# nixie.net
KiCad netlist of a schematic drawn in EAGLE
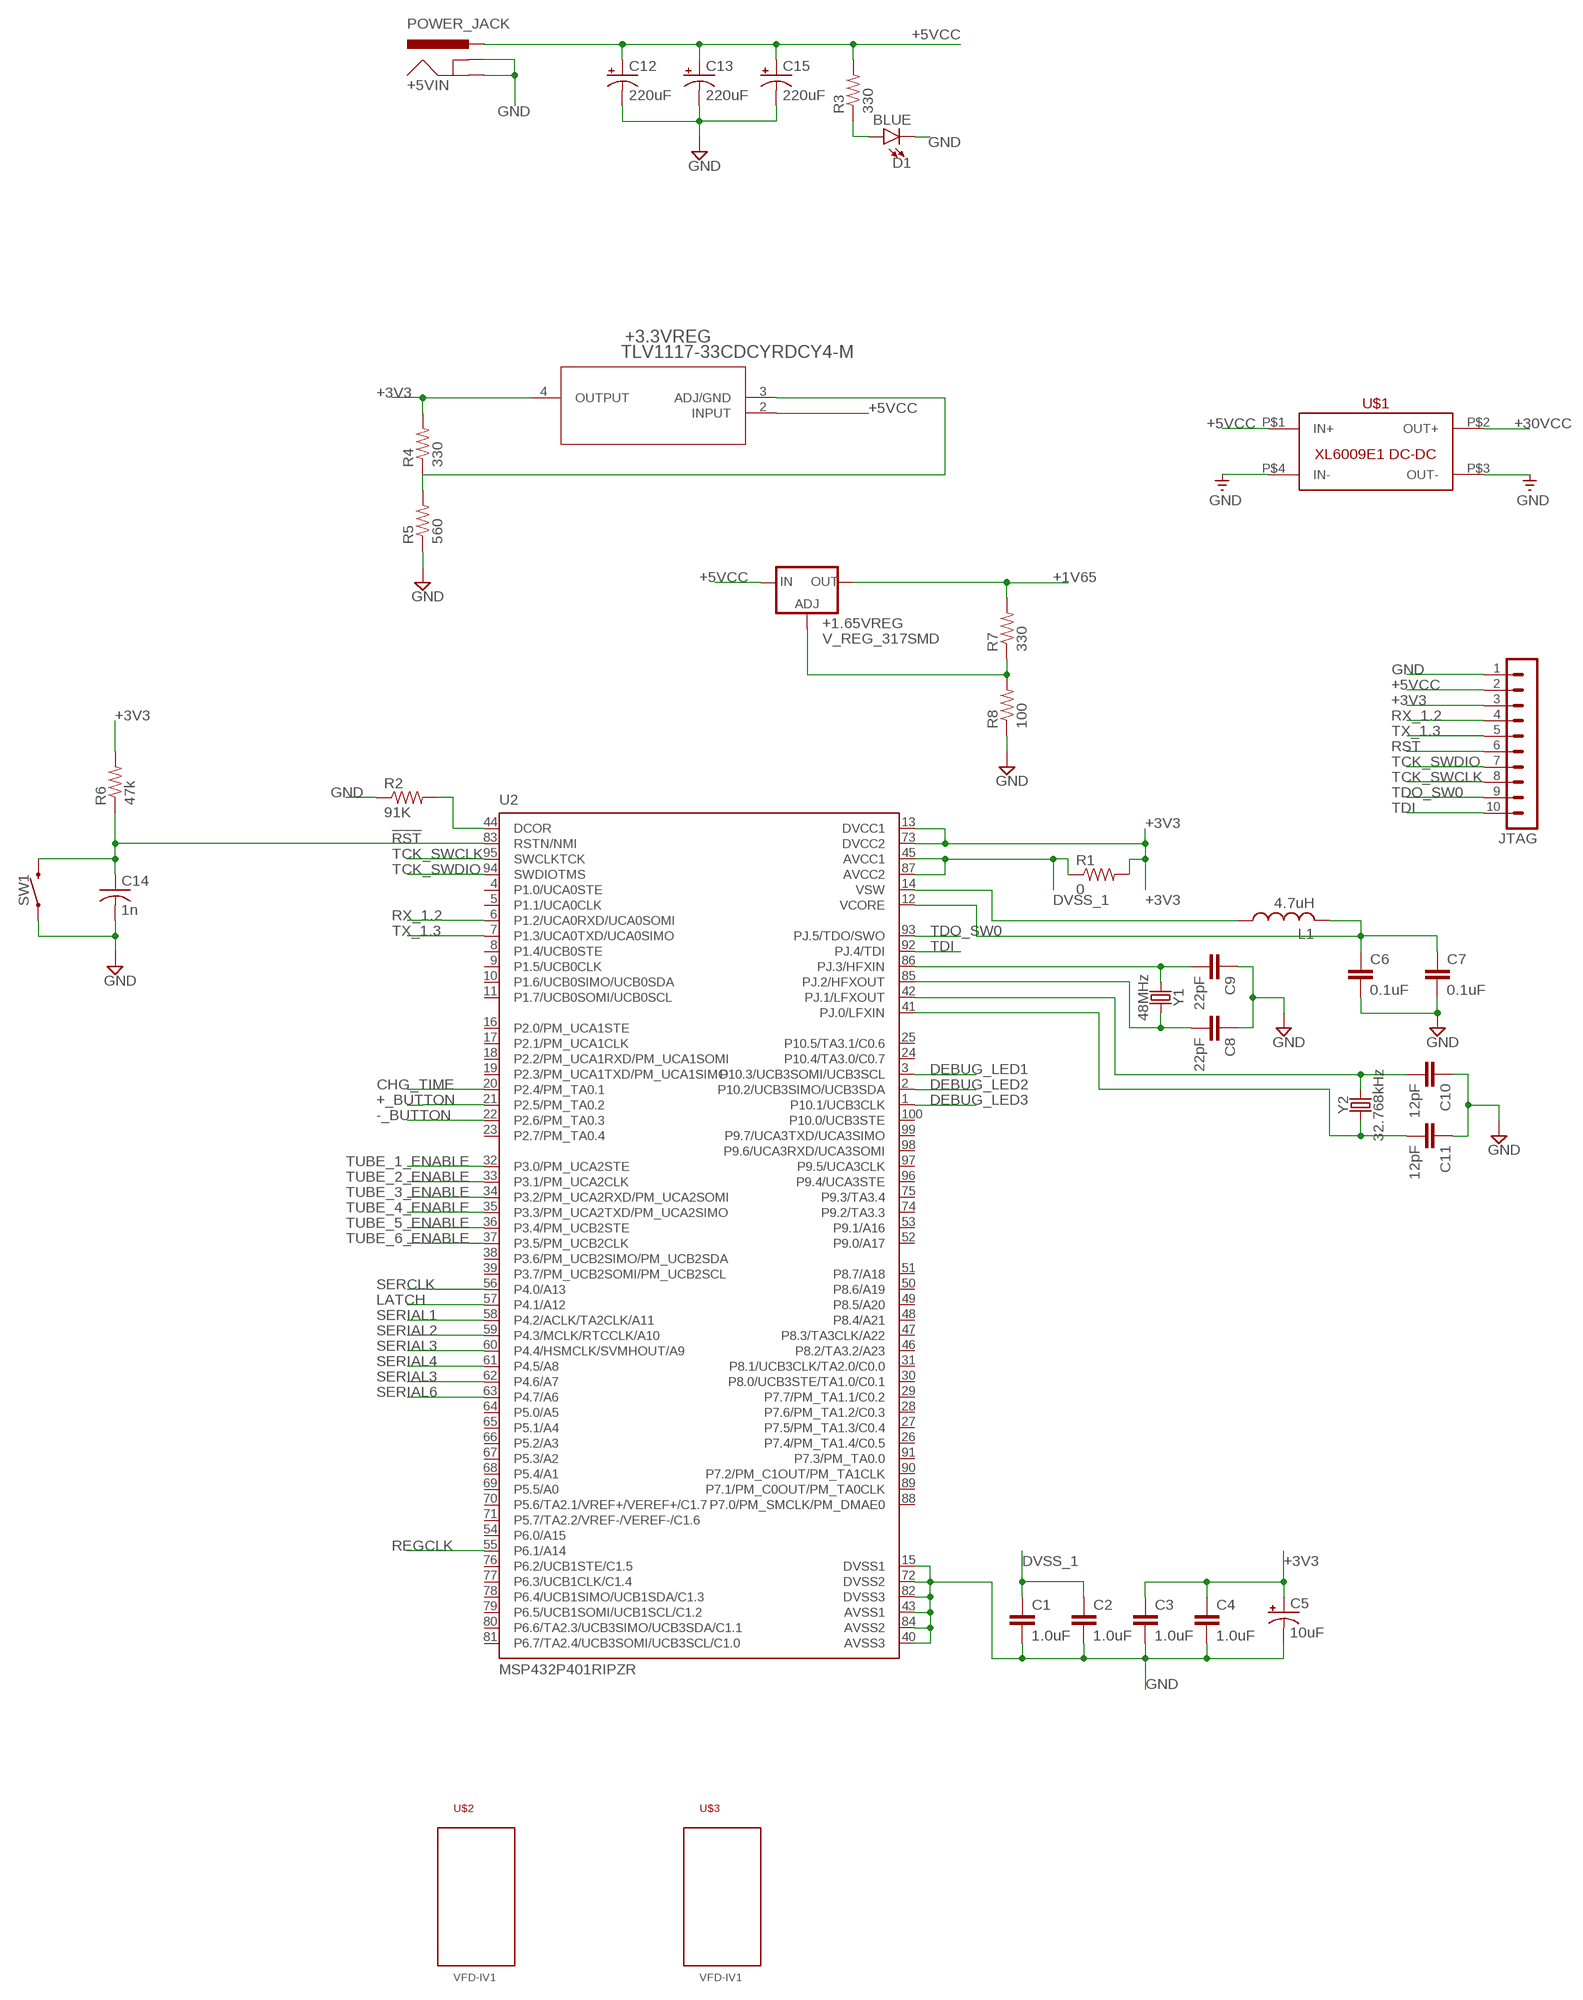
[diagram p0: schematic, sheet 1, part 1 of 2]
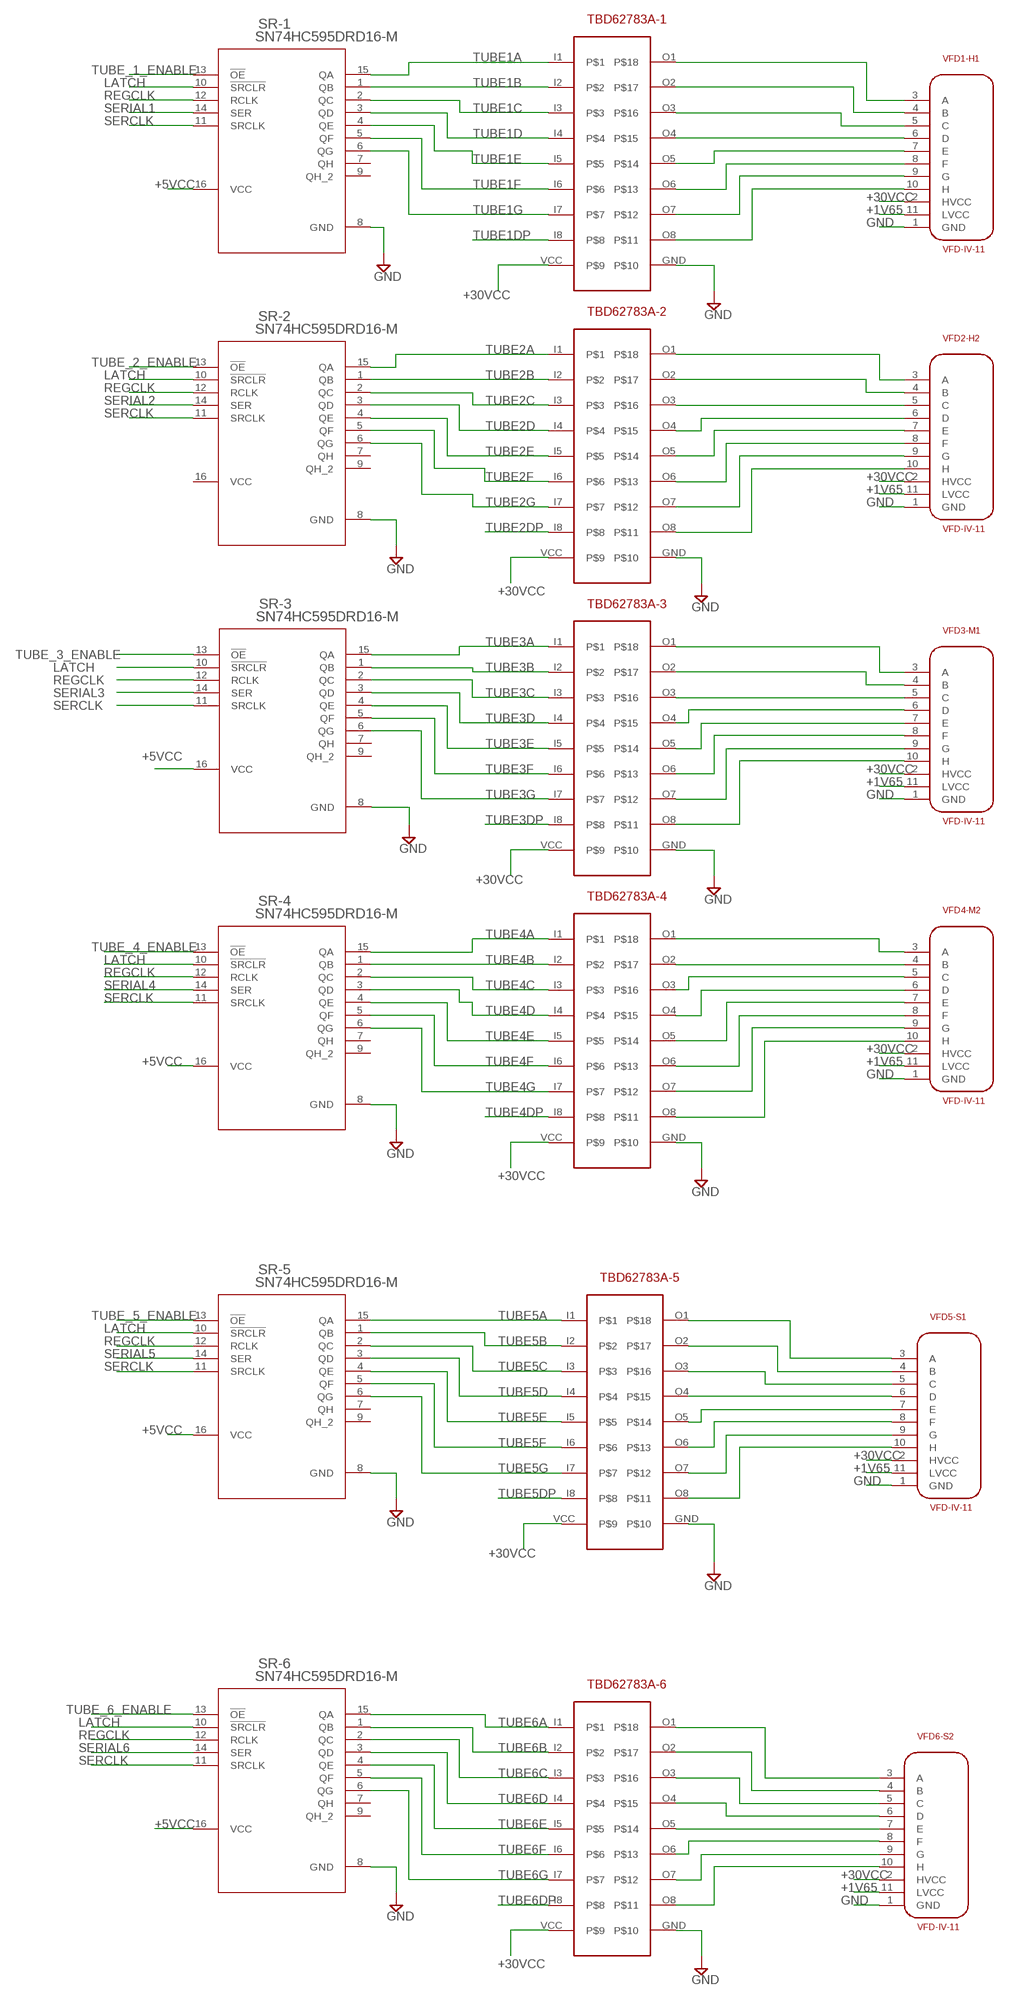
[diagram p1: schematic, sheet 1, part 2 of 2]

(export (version "E")
  (design (tool "Eeschema 10.0.6"))
  (components
    (comp (ref "+1.65VREG")
      (value "V_REG_317SMD")
      (footprint "eagle-import:SOT223")
      (libsource (lib "eagle-import") (part "V_REG_317SMD"))
    )
    (comp (ref "+3.3VREG")
      (value "TLV1117-33CDCYRDCY4-M")
      (footprint "eagle-import:DCY4-M")
      (fields (field (name "MANUFACTURER_PART_NUMBER") "TLV111733CDCYR"))
      (libsource (lib "eagle-import") (part "TLV1117-33CDCYRDCY4-M"))
    )
    (comp (ref "+5VIN")
      (value "POWER_JACK")
      (footprint "eagle-import:POWER_JACK_PTH")
      (libsource (lib "eagle-import") (part "POWER_JACK"))
    )
    (comp (ref "C1")
      (value "1.0uF")
      (footprint "eagle-import:0805")
      (libsource (lib "eagle-import") (part "1.0UF-0805-25V-(+80/-20%)"))
    )
    (comp (ref "C2")
      (value "1.0uF")
      (footprint "eagle-import:0805")
      (libsource (lib "eagle-import") (part "1.0UF-0805-25V-(+80/-20%)"))
    )
    (comp (ref "C3")
      (value "1.0uF")
      (footprint "eagle-import:0805")
      (libsource (lib "eagle-import") (part "1.0UF-0805-25V-(+80/-20%)"))
    )
    (comp (ref "C4")
      (value "1.0uF")
      (footprint "eagle-import:0805")
      (libsource (lib "eagle-import") (part "1.0UF-0805-25V-(+80/-20%)"))
    )
    (comp (ref "C5")
      (value "10uF")
      (footprint "eagle-import:EIA3216")
      (libsource (lib "eagle-import") (part "10UF-POLAR-EIA3216-16V-10%(TANT)"))
    )
    (comp (ref "C6")
      (value "0.1uF")
      (footprint "eagle-import:0603")
      (libsource (lib "eagle-import") (part "0.1UF-0603-25V-(+80/-20%)"))
    )
    (comp (ref "C7")
      (value "0.1uF")
      (footprint "eagle-import:0603")
      (libsource (lib "eagle-import") (part "0.1UF-0603-25V-(+80/-20%)"))
    )
    (comp (ref "C8")
      (value "22pF")
      (footprint "eagle-import:0603")
      (libsource (lib "eagle-import") (part "22PF-0603-50V-5%"))
    )
    (comp (ref "C9")
      (value "22pF")
      (footprint "eagle-import:0603")
      (libsource (lib "eagle-import") (part "22PF-0603-50V-5%"))
    )
    (comp (ref "C10")
      (value "12pF")
      (footprint "eagle-import:0603")
      (libsource (lib "eagle-import") (part "12PF-0603-50V-5%"))
    )
    (comp (ref "C11")
      (value "12pF")
      (footprint "eagle-import:0603")
      (libsource (lib "eagle-import") (part "12PF-0603-50V-5%"))
    )
    (comp (ref "C12")
      (value "220uF")
      (footprint "eagle-import:E2-5")
      (libsource (lib "eagle-import") (part "CPOL-USE2-5"))
    )
    (comp (ref "C13")
      (value "220uF")
      (footprint "eagle-import:E2-5")
      (libsource (lib "eagle-import") (part "CPOL-USE2-5"))
    )
    (comp (ref "C14")
      (value "1n")
      (footprint "eagle-import:C0805K")
      (libsource (lib "eagle-import") (part "C-USC0805K"))
    )
    (comp (ref "C15")
      (value "220uF")
      (footprint "eagle-import:E2-5")
      (libsource (lib "eagle-import") (part "CPOL-USE2-5"))
    )
    (comp (ref "D1")
      (value "BLUE")
      (footprint "eagle-import:LED-1206")
      (libsource (lib "eagle-import") (part "LED-BLUE1206"))
    )
    (comp (ref "JTAG")
      (value "MA10-1")
      (footprint "eagle-import:MA10-1")
      (libsource (lib "eagle-import") (part "MA10-1"))
    )
    (comp (ref "L1")
      (value "4.7uH")
      (footprint "eagle-import:L0603")
      (libsource (lib "eagle-import") (part "L-USL0603"))
    )
    (comp (ref "R1")
      (value "0")
      (footprint "eagle-import:MINI_MELF-0204W")
      (libsource (lib "eagle-import") (part "R-US_MELF0204W"))
    )
    (comp (ref "R2")
      (value "91K")
      (footprint "eagle-import:MINI_MELF-0204W")
      (libsource (lib "eagle-import") (part "R-US_MELF0204W"))
    )
    (comp (ref "R3")
      (value "330")
      (footprint "eagle-import:MINI_MELF-0204W")
      (libsource (lib "eagle-import") (part "R-US_MELF0204W"))
    )
    (comp (ref "R4")
      (value "330")
      (footprint "eagle-import:MINI_MELF-0204W")
      (libsource (lib "eagle-import") (part "R-US_MELF0204W"))
    )
    (comp (ref "R5")
      (value "560")
      (footprint "eagle-import:MINI_MELF-0204W")
      (libsource (lib "eagle-import") (part "R-US_MELF0204W"))
    )
    (comp (ref "R6")
      (value "47k")
      (footprint "eagle-import:MINI_MELF-0204W")
      (libsource (lib "eagle-import") (part "R-US_MELF0204W"))
    )
    (comp (ref "R7")
      (value "330")
      (footprint "eagle-import:MINI_MELF-0204W")
      (libsource (lib "eagle-import") (part "R-US_MELF0204W"))
    )
    (comp (ref "R8")
      (value "100")
      (footprint "eagle-import:MINI_MELF-0204W")
      (libsource (lib "eagle-import") (part "R-US_MELF0204W"))
    )
    (comp (ref "SR-1")
      (value "SN74HC595DRD16-M")
      (footprint "eagle-import:D16-M")
      (fields (field (name "MANUFACTURER_PART_NUMBER") "SN74HC595DR"))
      (libsource (lib "eagle-import") (part "SN74HC595DRD16-M"))
    )
    (comp (ref "SR-2")
      (value "SN74HC595DRD16-M")
      (footprint "eagle-import:D16-M")
      (fields (field (name "MANUFACTURER_PART_NUMBER") "SN74HC595DR"))
      (libsource (lib "eagle-import") (part "SN74HC595DRD16-M"))
    )
    (comp (ref "SR-3")
      (value "SN74HC595DRD16-M")
      (footprint "eagle-import:D16-M")
      (fields (field (name "MANUFACTURER_PART_NUMBER") "SN74HC595DR"))
      (libsource (lib "eagle-import") (part "SN74HC595DRD16-M"))
    )
    (comp (ref "SR-4")
      (value "SN74HC595DRD16-M")
      (footprint "eagle-import:D16-M")
      (fields (field (name "MANUFACTURER_PART_NUMBER") "SN74HC595DR"))
      (libsource (lib "eagle-import") (part "SN74HC595DRD16-M"))
    )
    (comp (ref "SR-5")
      (value "SN74HC595DRD16-M")
      (footprint "eagle-import:D16-M")
      (fields (field (name "MANUFACTURER_PART_NUMBER") "SN74HC595DR"))
      (libsource (lib "eagle-import") (part "SN74HC595DRD16-M"))
    )
    (comp (ref "SR-6")
      (value "SN74HC595DRD16-M")
      (footprint "eagle-import:D16-M")
      (fields (field (name "MANUFACTURER_PART_NUMBER") "SN74HC595DR"))
      (libsource (lib "eagle-import") (part "SN74HC595DRD16-M"))
    )
    (comp (ref "SW1")
      (value "MOMENTARY-SWITCH-SPST-SMD-6.2MM-TALL")
      (footprint "eagle-import:TACTILE_SWITCH_SMD_6.2MM_TALL")
      (libsource (lib "eagle-import") (part "MOMENTARY-SWITCH-SPST-SMD-6.2MM-TALL"))
    )
    (comp (ref "TBD62783A-1")
      (value "TBD62783AFG")
      (footprint "eagle-import:TBD62783AFG")
      (libsource (lib "eagle-import") (part "TBD62783AFG_TBD62783AFG"))
    )
    (comp (ref "TBD62783A-2")
      (value "TBD62783AFG")
      (footprint "eagle-import:TBD62783AFG")
      (libsource (lib "eagle-import") (part "TBD62783AFG_TBD62783AFG"))
    )
    (comp (ref "TBD62783A-3")
      (value "TBD62783AFG")
      (footprint "eagle-import:TBD62783AFG")
      (libsource (lib "eagle-import") (part "TBD62783AFG_TBD62783AFG"))
    )
    (comp (ref "TBD62783A-4")
      (value "TBD62783AFG")
      (footprint "eagle-import:TBD62783AFG")
      (libsource (lib "eagle-import") (part "TBD62783AFG_TBD62783AFG"))
    )
    (comp (ref "TBD62783A-5")
      (value "TBD62783AFG")
      (footprint "eagle-import:TBD62783AFG")
      (libsource (lib "eagle-import") (part "TBD62783AFG_TBD62783AFG"))
    )
    (comp (ref "TBD62783A-6")
      (value "TBD62783AFG")
      (footprint "eagle-import:TBD62783AFG")
      (libsource (lib "eagle-import") (part "TBD62783AFG_TBD62783AFG"))
    )
    (comp (ref "U$1")
      (value "XL6009E1")
      (footprint "eagle-import:XL6009E1")
      (libsource (lib "eagle-import") (part "XL6009E1"))
    )
    (comp (ref "U$2")
      (value "VFD-IV-1")
      (footprint "eagle-import:VFD-IV1")
      (libsource (lib "eagle-import") (part "VFD-IV-1"))
    )
    (comp (ref "U$3")
      (value "VFD-IV-1")
      (footprint "eagle-import:VFD-IV1")
      (libsource (lib "eagle-import") (part "VFD-IV-1"))
    )
    (comp (ref "U2")
      (value "MSP432P401RIPZR")
      (footprint "eagle-import:QFP50P1600X1600X160-100N")
      (fields (field (name "MF") "Texas Instruments"))
      (libsource (lib "eagle-import") (part "MSP432P401RIPZR"))
    )
    (comp (ref "VFD1-H1")
      (value "VFD-IV-11")
      (footprint "eagle-import:VFD-IV11")
      (libsource (lib "eagle-import") (part "VFD-IV-11"))
    )
    (comp (ref "VFD2-H2")
      (value "VFD-IV-11")
      (footprint "eagle-import:VFD-IV11")
      (libsource (lib "eagle-import") (part "VFD-IV-11"))
    )
    (comp (ref "VFD3-M1")
      (value "VFD-IV-11")
      (footprint "eagle-import:VFD-IV11")
      (libsource (lib "eagle-import") (part "VFD-IV-11"))
    )
    (comp (ref "VFD4-M2")
      (value "VFD-IV-11")
      (footprint "eagle-import:VFD-IV11")
      (libsource (lib "eagle-import") (part "VFD-IV-11"))
    )
    (comp (ref "VFD5-S1")
      (value "VFD-IV-11")
      (footprint "eagle-import:VFD-IV11")
      (libsource (lib "eagle-import") (part "VFD-IV-11"))
    )
    (comp (ref "VFD6-S2")
      (value "VFD-IV-11")
      (footprint "eagle-import:VFD-IV11")
      (libsource (lib "eagle-import") (part "VFD-IV-11"))
    )
    (comp (ref "Y1")
      (value "48MHz")
      (footprint "eagle-import:CRYSTAL-SMD-3.2X2.5MM")
      (libsource (lib "eagle-import") (part "CRYSTALSMD-3.2X2.5"))
    )
    (comp (ref "Y2")
      (value "32.768kHz")
      (footprint "eagle-import:CRYSTAL-SMD-3.2X1.5MM")
      (libsource (lib "eagle-import") (part "CRYSTAL-32.768KHZSMD-3.2X1.5"))
    )
  )
  (nets
    (net (code "1") (name "/+1V65") (class "Default")
      (node (ref "+1.65VREG") (pin "2") (pinfunction "OUT_2") (pintype "output"))
      (node (ref "R7") (pin "2") (pinfunction "2_2") (pintype "passive"))
      (node (ref "VFD1-H1") (pin "11") (pinfunction "LVCC_11") (pintype "bidirectional"))
      (node (ref "VFD2-H2") (pin "11") (pinfunction "LVCC_11") (pintype "bidirectional"))
      (node (ref "VFD3-M1") (pin "11") (pinfunction "LVCC_11") (pintype "bidirectional"))
      (node (ref "VFD4-M2") (pin "11") (pinfunction "LVCC_11") (pintype "bidirectional"))
      (node (ref "VFD5-S1") (pin "11") (pinfunction "LVCC_11") (pintype "bidirectional"))
      (node (ref "VFD6-S2") (pin "11") (pinfunction "LVCC_11") (pintype "bidirectional"))
    )
    (net (code "2") (name "/+3V3") (class "Default")
      (node (ref "+3.3VREG") (pin "4") (pinfunction "OUTPUT_4") (pintype "output"))
      (node (ref "C3") (pin "1") (pinfunction "1_1") (pintype "passive"))
      (node (ref "C4") (pin "1") (pinfunction "1_1") (pintype "passive"))
      (node (ref "C5") (pin "+") (pinfunction "+_+") (pintype "passive"))
      (node (ref "JTAG") (pin "3") (pinfunction "3_3") (pintype "passive"))
      (node (ref "R1") (pin "2") (pinfunction "2_2") (pintype "passive"))
      (node (ref "R4") (pin "2") (pinfunction "2_2") (pintype "passive"))
      (node (ref "R6") (pin "2") (pinfunction "2_2") (pintype "passive"))
      (node (ref "U2") (pin "13") (pinfunction "DVCC1_13") (pintype "power_in"))
      (node (ref "U2") (pin "73") (pinfunction "DVCC2_73") (pintype "power_in"))
    )
    (net (code "3") (name "/+5VCC") (class "Default")
      (node (ref "+1.65VREG") (pin "3") (pinfunction "IN_3") (pintype "input"))
      (node (ref "+3.3VREG") (pin "2") (pinfunction "INPUT_2") (pintype "input"))
      (node (ref "+5VIN") (pin "PWR") (pinfunction "PWR_PWR") (pintype "bidirectional"))
      (node (ref "C12") (pin "+") (pinfunction "+_+") (pintype "passive"))
      (node (ref "C13") (pin "+") (pinfunction "+_+") (pintype "passive"))
      (node (ref "C15") (pin "+") (pinfunction "+_+") (pintype "passive"))
      (node (ref "JTAG") (pin "2") (pinfunction "2_2") (pintype "passive"))
      (node (ref "R3") (pin "2") (pinfunction "2_2") (pintype "passive"))
      (node (ref "SR-1") (pin "16") (pinfunction "VCC_16") (pintype "power_in"))
      (node (ref "SR-3") (pin "16") (pinfunction "VCC_16") (pintype "power_in"))
      (node (ref "SR-4") (pin "16") (pinfunction "VCC_16") (pintype "power_in"))
      (node (ref "SR-5") (pin "16") (pinfunction "VCC_16") (pintype "power_in"))
      (node (ref "SR-6") (pin "16") (pinfunction "VCC_16") (pintype "power_in"))
      (node (ref "U$1") (pin "P$1") (pinfunction "IN+_P$1") (pintype "bidirectional"))
    )
    (net (code "4") (name "/+30VCC") (class "Default")
      (node (ref "TBD62783A-1") (pin "VCC") (pinfunction "P$9_VCC") (pintype "bidirectional"))
      (node (ref "TBD62783A-2") (pin "VCC") (pinfunction "P$9_VCC") (pintype "bidirectional"))
      (node (ref "TBD62783A-3") (pin "VCC") (pinfunction "P$9_VCC") (pintype "bidirectional"))
      (node (ref "TBD62783A-4") (pin "VCC") (pinfunction "P$9_VCC") (pintype "bidirectional"))
      (node (ref "TBD62783A-5") (pin "VCC") (pinfunction "P$9_VCC") (pintype "bidirectional"))
      (node (ref "TBD62783A-6") (pin "VCC") (pinfunction "P$9_VCC") (pintype "bidirectional"))
      (node (ref "U$1") (pin "P$2") (pinfunction "OUT+_P$2") (pintype "bidirectional"))
      (node (ref "VFD1-H1") (pin "2") (pinfunction "HVCC_2") (pintype "bidirectional"))
      (node (ref "VFD2-H2") (pin "2") (pinfunction "HVCC_2") (pintype "bidirectional"))
      (node (ref "VFD3-M1") (pin "2") (pinfunction "HVCC_2") (pintype "bidirectional"))
      (node (ref "VFD4-M2") (pin "2") (pinfunction "HVCC_2") (pintype "bidirectional"))
      (node (ref "VFD5-S1") (pin "2") (pinfunction "HVCC_2") (pintype "bidirectional"))
      (node (ref "VFD6-S2") (pin "2") (pinfunction "HVCC_2") (pintype "bidirectional"))
    )
    (net (code "5") (name "/+_BUTTON") (class "Default")
      (node (ref "U2") (pin "21") (pinfunction "P2.5/PM_TA0.2_21") (pintype "bidirectional"))
    )
    (net (code "6") (name "/-_BUTTON") (class "Default")
      (node (ref "U2") (pin "22") (pinfunction "P2.6/PM_TA0.3_22") (pintype "bidirectional"))
    )
    (net (code "7") (name "/CHG_TIME") (class "Default")
      (node (ref "U2") (pin "20") (pinfunction "P2.4/PM_TA0.1_20") (pintype "bidirectional"))
    )
    (net (code "8") (name "/DEBUG_LED1") (class "Default")
      (node (ref "U2") (pin "3") (pinfunction "P10.3/UCB3SOMI/UCB3SCL_3") (pintype "bidirectional"))
    )
    (net (code "9") (name "/DEBUG_LED2") (class "Default")
      (node (ref "U2") (pin "2") (pinfunction "P10.2/UCB3SIMO/UCB3SDA_2") (pintype "bidirectional"))
    )
    (net (code "10") (name "/DEBUG_LED3") (class "Default")
      (node (ref "U2") (pin "1") (pinfunction "P10.1/UCB3CLK_1") (pintype "bidirectional"))
    )
    (net (code "11") (name "/DVSS_1") (class "Default")
      (node (ref "C1") (pin "1") (pinfunction "1_1") (pintype "passive"))
      (node (ref "C2") (pin "1") (pinfunction "1_1") (pintype "passive"))
      (node (ref "R1") (pin "1") (pinfunction "1_1") (pintype "passive"))
      (node (ref "U2") (pin "45") (pinfunction "AVCC1_45") (pintype "power_in"))
      (node (ref "U2") (pin "87") (pinfunction "AVCC2_87") (pintype "power_in"))
    )
    (net (code "12") (name "/LATCH") (class "Default")
      (node (ref "SR-1") (pin "10") (pinfunction "~{SRCLR}_10") (pintype "input"))
      (node (ref "SR-2") (pin "10") (pinfunction "~{SRCLR}_10") (pintype "input"))
      (node (ref "SR-3") (pin "10") (pinfunction "~{SRCLR}_10") (pintype "input"))
      (node (ref "SR-4") (pin "10") (pinfunction "~{SRCLR}_10") (pintype "input"))
      (node (ref "SR-5") (pin "10") (pinfunction "~{SRCLR}_10") (pintype "input"))
      (node (ref "SR-6") (pin "10") (pinfunction "~{SRCLR}_10") (pintype "input"))
      (node (ref "U2") (pin "57") (pinfunction "P4.1/A12_57") (pintype "bidirectional"))
    )
    (net (code "13") (name "/REGCLK") (class "Default")
      (node (ref "SR-1") (pin "12") (pinfunction "RCLK_12") (pintype "input"))
      (node (ref "SR-2") (pin "12") (pinfunction "RCLK_12") (pintype "input"))
      (node (ref "SR-3") (pin "12") (pinfunction "RCLK_12") (pintype "input"))
      (node (ref "SR-4") (pin "12") (pinfunction "RCLK_12") (pintype "input"))
      (node (ref "SR-5") (pin "12") (pinfunction "RCLK_12") (pintype "input"))
      (node (ref "SR-6") (pin "12") (pinfunction "RCLK_12") (pintype "input"))
      (node (ref "U2") (pin "55") (pinfunction "P6.1/A14_55") (pintype "bidirectional"))
    )
    (net (code "14") (name "/RST") (class "Default")
      (node (ref "JTAG") (pin "6") (pinfunction "6_6") (pintype "passive"))
    )
    (net (code "15") (name "/RX_1.2") (class "Default")
      (node (ref "JTAG") (pin "4") (pinfunction "4_4") (pintype "passive"))
      (node (ref "U2") (pin "6") (pinfunction "P1.2/UCA0RXD/UCA0SOMI_6") (pintype "bidirectional"))
    )
    (net (code "16") (name "/SERCLK") (class "Default")
      (node (ref "SR-1") (pin "11") (pinfunction "SRCLK_11") (pintype "input"))
      (node (ref "SR-2") (pin "11") (pinfunction "SRCLK_11") (pintype "input"))
      (node (ref "SR-3") (pin "11") (pinfunction "SRCLK_11") (pintype "input"))
      (node (ref "SR-4") (pin "11") (pinfunction "SRCLK_11") (pintype "input"))
      (node (ref "SR-5") (pin "11") (pinfunction "SRCLK_11") (pintype "input"))
      (node (ref "SR-6") (pin "11") (pinfunction "SRCLK_11") (pintype "input"))
      (node (ref "U2") (pin "56") (pinfunction "P4.0/A13_56") (pintype "bidirectional"))
    )
    (net (code "17") (name "/SERIAL1") (class "Default")
      (node (ref "SR-1") (pin "14") (pinfunction "SER_14") (pintype "input"))
      (node (ref "U2") (pin "58") (pinfunction "P4.2/ACLK/TA2CLK/A11_58") (pintype "bidirectional"))
    )
    (net (code "18") (name "/SERIAL2") (class "Default")
      (node (ref "SR-2") (pin "14") (pinfunction "SER_14") (pintype "input"))
      (node (ref "U2") (pin "59") (pinfunction "P4.3/MCLK/RTCCLK/A10_59") (pintype "bidirectional"))
    )
    (net (code "19") (name "/SERIAL3") (class "Default")
      (node (ref "SR-3") (pin "14") (pinfunction "SER_14") (pintype "input"))
      (node (ref "U2") (pin "60") (pinfunction "P4.4/HSMCLK/SVMHOUT/A9_60") (pintype "bidirectional"))
      (node (ref "U2") (pin "62") (pinfunction "P4.6/A7_62") (pintype "bidirectional"))
    )
    (net (code "20") (name "/SERIAL4") (class "Default")
      (node (ref "SR-4") (pin "14") (pinfunction "SER_14") (pintype "input"))
      (node (ref "U2") (pin "61") (pinfunction "P4.5/A8_61") (pintype "bidirectional"))
    )
    (net (code "21") (name "/SERIAL5") (class "Default")
      (node (ref "SR-5") (pin "14") (pinfunction "SER_14") (pintype "input"))
    )
    (net (code "22") (name "/SERIAL6") (class "Default")
      (node (ref "SR-6") (pin "14") (pinfunction "SER_14") (pintype "input"))
      (node (ref "U2") (pin "63") (pinfunction "P4.7/A6_63") (pintype "bidirectional"))
    )
    (net (code "23") (name "/TCK_SWCLK") (class "Default")
      (node (ref "JTAG") (pin "8") (pinfunction "8_8") (pintype "passive"))
      (node (ref "U2") (pin "95") (pinfunction "SWCLKTCK_95") (pintype "bidirectional"))
    )
    (net (code "24") (name "/TCK_SWDIO") (class "Default")
      (node (ref "JTAG") (pin "7") (pinfunction "7_7") (pintype "passive"))
      (node (ref "U2") (pin "94") (pinfunction "SWDIOTMS_94") (pintype "bidirectional"))
    )
    (net (code "25") (name "/TDI") (class "Default")
      (node (ref "JTAG") (pin "10") (pinfunction "10_10") (pintype "passive"))
      (node (ref "U2") (pin "92") (pinfunction "PJ.4/TDI_92") (pintype "bidirectional"))
    )
    (net (code "26") (name "/TDO_SW0") (class "Default")
      (node (ref "JTAG") (pin "9") (pinfunction "9_9") (pintype "passive"))
      (node (ref "U2") (pin "93") (pinfunction "PJ.5/TDO/SWO_93") (pintype "bidirectional"))
    )
    (net (code "27") (name "/TUBE1A") (class "Default")
      (node (ref "SR-1") (pin "15") (pinfunction "QA_15") (pintype "output"))
      (node (ref "TBD62783A-1") (pin "I1") (pinfunction "P$1_I1") (pintype "bidirectional"))
    )
    (net (code "28") (name "/TUBE1B") (class "Default")
      (node (ref "SR-1") (pin "1") (pinfunction "QB_1") (pintype "output"))
      (node (ref "TBD62783A-1") (pin "I2") (pinfunction "P$2_I2") (pintype "bidirectional"))
    )
    (net (code "29") (name "/TUBE1C") (class "Default")
      (node (ref "SR-1") (pin "2") (pinfunction "QC_2") (pintype "output"))
      (node (ref "TBD62783A-1") (pin "I3") (pinfunction "P$3_I3") (pintype "bidirectional"))
    )
    (net (code "30") (name "/TUBE1D") (class "Default")
      (node (ref "SR-1") (pin "3") (pinfunction "QD_3") (pintype "output"))
      (node (ref "TBD62783A-1") (pin "I4") (pinfunction "P$4_I4") (pintype "bidirectional"))
    )
    (net (code "31") (name "/TUBE1DP") (class "Default")
      (node (ref "TBD62783A-1") (pin "I8") (pinfunction "P$8_I8") (pintype "bidirectional"))
    )
    (net (code "32") (name "/TUBE1E") (class "Default")
      (node (ref "SR-1") (pin "4") (pinfunction "QE_4") (pintype "output"))
      (node (ref "TBD62783A-1") (pin "I5") (pinfunction "P$5_I5") (pintype "bidirectional"))
    )
    (net (code "33") (name "/TUBE1F") (class "Default")
      (node (ref "SR-1") (pin "5") (pinfunction "QF_5") (pintype "output"))
      (node (ref "TBD62783A-1") (pin "I6") (pinfunction "P$6_I6") (pintype "bidirectional"))
    )
    (net (code "34") (name "/TUBE1G") (class "Default")
      (node (ref "SR-1") (pin "6") (pinfunction "QG_6") (pintype "output"))
      (node (ref "TBD62783A-1") (pin "I7") (pinfunction "P$7_I7") (pintype "bidirectional"))
    )
    (net (code "35") (name "/TUBE2A") (class "Default")
      (node (ref "SR-2") (pin "15") (pinfunction "QA_15") (pintype "output"))
      (node (ref "TBD62783A-2") (pin "I1") (pinfunction "P$1_I1") (pintype "bidirectional"))
    )
    (net (code "36") (name "/TUBE2B") (class "Default")
      (node (ref "SR-2") (pin "1") (pinfunction "QB_1") (pintype "output"))
      (node (ref "TBD62783A-2") (pin "I2") (pinfunction "P$2_I2") (pintype "bidirectional"))
    )
    (net (code "37") (name "/TUBE2C") (class "Default")
      (node (ref "SR-2") (pin "2") (pinfunction "QC_2") (pintype "output"))
      (node (ref "TBD62783A-2") (pin "I3") (pinfunction "P$3_I3") (pintype "bidirectional"))
    )
    (net (code "38") (name "/TUBE2D") (class "Default")
      (node (ref "SR-2") (pin "3") (pinfunction "QD_3") (pintype "output"))
      (node (ref "TBD62783A-2") (pin "I4") (pinfunction "P$4_I4") (pintype "bidirectional"))
    )
    (net (code "39") (name "/TUBE2DP") (class "Default")
      (node (ref "TBD62783A-2") (pin "I8") (pinfunction "P$8_I8") (pintype "bidirectional"))
    )
    (net (code "40") (name "/TUBE2E") (class "Default")
      (node (ref "SR-2") (pin "4") (pinfunction "QE_4") (pintype "output"))
      (node (ref "TBD62783A-2") (pin "I5") (pinfunction "P$5_I5") (pintype "bidirectional"))
    )
    (net (code "41") (name "/TUBE2F") (class "Default")
      (node (ref "SR-2") (pin "5") (pinfunction "QF_5") (pintype "output"))
      (node (ref "TBD62783A-2") (pin "I6") (pinfunction "P$6_I6") (pintype "bidirectional"))
    )
    (net (code "42") (name "/TUBE2G") (class "Default")
      (node (ref "SR-2") (pin "6") (pinfunction "QG_6") (pintype "output"))
      (node (ref "TBD62783A-2") (pin "I7") (pinfunction "P$7_I7") (pintype "bidirectional"))
    )
    (net (code "43") (name "/TUBE3A") (class "Default")
      (node (ref "SR-3") (pin "15") (pinfunction "QA_15") (pintype "output"))
      (node (ref "TBD62783A-3") (pin "I1") (pinfunction "P$1_I1") (pintype "bidirectional"))
    )
    (net (code "44") (name "/TUBE3B") (class "Default")
      (node (ref "SR-3") (pin "1") (pinfunction "QB_1") (pintype "output"))
      (node (ref "TBD62783A-3") (pin "I2") (pinfunction "P$2_I2") (pintype "bidirectional"))
    )
    (net (code "45") (name "/TUBE3C") (class "Default")
      (node (ref "SR-3") (pin "2") (pinfunction "QC_2") (pintype "output"))
      (node (ref "TBD62783A-3") (pin "I3") (pinfunction "P$3_I3") (pintype "bidirectional"))
    )
    (net (code "46") (name "/TUBE3D") (class "Default")
      (node (ref "SR-3") (pin "3") (pinfunction "QD_3") (pintype "output"))
      (node (ref "TBD62783A-3") (pin "I4") (pinfunction "P$4_I4") (pintype "bidirectional"))
    )
    (net (code "47") (name "/TUBE3DP") (class "Default")
      (node (ref "TBD62783A-3") (pin "I8") (pinfunction "P$8_I8") (pintype "bidirectional"))
    )
    (net (code "48") (name "/TUBE3E") (class "Default")
      (node (ref "SR-3") (pin "4") (pinfunction "QE_4") (pintype "output"))
      (node (ref "TBD62783A-3") (pin "I5") (pinfunction "P$5_I5") (pintype "bidirectional"))
    )
    (net (code "49") (name "/TUBE3F") (class "Default")
      (node (ref "SR-3") (pin "5") (pinfunction "QF_5") (pintype "output"))
      (node (ref "TBD62783A-3") (pin "I6") (pinfunction "P$6_I6") (pintype "bidirectional"))
    )
    (net (code "50") (name "/TUBE3G") (class "Default")
      (node (ref "SR-3") (pin "6") (pinfunction "QG_6") (pintype "output"))
      (node (ref "TBD62783A-3") (pin "I7") (pinfunction "P$7_I7") (pintype "bidirectional"))
    )
    (net (code "51") (name "/TUBE4A") (class "Default")
      (node (ref "SR-4") (pin "15") (pinfunction "QA_15") (pintype "output"))
      (node (ref "TBD62783A-4") (pin "I1") (pinfunction "P$1_I1") (pintype "bidirectional"))
    )
    (net (code "52") (name "/TUBE4B") (class "Default")
      (node (ref "SR-4") (pin "1") (pinfunction "QB_1") (pintype "output"))
      (node (ref "TBD62783A-4") (pin "I2") (pinfunction "P$2_I2") (pintype "bidirectional"))
    )
    (net (code "53") (name "/TUBE4C") (class "Default")
      (node (ref "SR-4") (pin "2") (pinfunction "QC_2") (pintype "output"))
      (node (ref "TBD62783A-4") (pin "I3") (pinfunction "P$3_I3") (pintype "bidirectional"))
    )
    (net (code "54") (name "/TUBE4D") (class "Default")
      (node (ref "SR-4") (pin "3") (pinfunction "QD_3") (pintype "output"))
      (node (ref "TBD62783A-4") (pin "I4") (pinfunction "P$4_I4") (pintype "bidirectional"))
    )
    (net (code "55") (name "/TUBE4DP") (class "Default")
      (node (ref "TBD62783A-4") (pin "I8") (pinfunction "P$8_I8") (pintype "bidirectional"))
    )
    (net (code "56") (name "/TUBE4E") (class "Default")
      (node (ref "SR-4") (pin "4") (pinfunction "QE_4") (pintype "output"))
      (node (ref "TBD62783A-4") (pin "I5") (pinfunction "P$5_I5") (pintype "bidirectional"))
    )
    (net (code "57") (name "/TUBE4F") (class "Default")
      (node (ref "SR-4") (pin "5") (pinfunction "QF_5") (pintype "output"))
      (node (ref "TBD62783A-4") (pin "I6") (pinfunction "P$6_I6") (pintype "bidirectional"))
    )
    (net (code "58") (name "/TUBE4G") (class "Default")
      (node (ref "SR-4") (pin "6") (pinfunction "QG_6") (pintype "output"))
      (node (ref "TBD62783A-4") (pin "I7") (pinfunction "P$7_I7") (pintype "bidirectional"))
    )
    (net (code "59") (name "/TUBE5A") (class "Default")
      (node (ref "SR-5") (pin "15") (pinfunction "QA_15") (pintype "output"))
      (node (ref "TBD62783A-5") (pin "I1") (pinfunction "P$1_I1") (pintype "bidirectional"))
    )
    (net (code "60") (name "/TUBE5B") (class "Default")
      (node (ref "SR-5") (pin "1") (pinfunction "QB_1") (pintype "output"))
      (node (ref "TBD62783A-5") (pin "I2") (pinfunction "P$2_I2") (pintype "bidirectional"))
    )
    (net (code "61") (name "/TUBE5C") (class "Default")
      (node (ref "SR-5") (pin "2") (pinfunction "QC_2") (pintype "output"))
      (node (ref "TBD62783A-5") (pin "I3") (pinfunction "P$3_I3") (pintype "bidirectional"))
    )
    (net (code "62") (name "/TUBE5D") (class "Default")
      (node (ref "SR-5") (pin "3") (pinfunction "QD_3") (pintype "output"))
      (node (ref "TBD62783A-5") (pin "I4") (pinfunction "P$4_I4") (pintype "bidirectional"))
    )
    (net (code "63") (name "/TUBE5DP") (class "Default")
      (node (ref "TBD62783A-5") (pin "I8") (pinfunction "P$8_I8") (pintype "bidirectional"))
    )
    (net (code "64") (name "/TUBE5E") (class "Default")
      (node (ref "SR-5") (pin "4") (pinfunction "QE_4") (pintype "output"))
      (node (ref "TBD62783A-5") (pin "I5") (pinfunction "P$5_I5") (pintype "bidirectional"))
    )
    (net (code "65") (name "/TUBE5F") (class "Default")
      (node (ref "SR-5") (pin "5") (pinfunction "QF_5") (pintype "output"))
      (node (ref "TBD62783A-5") (pin "I6") (pinfunction "P$6_I6") (pintype "bidirectional"))
    )
    (net (code "66") (name "/TUBE5G") (class "Default")
      (node (ref "SR-5") (pin "6") (pinfunction "QG_6") (pintype "output"))
      (node (ref "TBD62783A-5") (pin "I7") (pinfunction "P$7_I7") (pintype "bidirectional"))
    )
    (net (code "67") (name "/TUBE6A") (class "Default")
      (node (ref "SR-6") (pin "15") (pinfunction "QA_15") (pintype "output"))
      (node (ref "TBD62783A-6") (pin "I1") (pinfunction "P$1_I1") (pintype "bidirectional"))
    )
    (net (code "68") (name "/TUBE6B") (class "Default")
      (node (ref "SR-6") (pin "1") (pinfunction "QB_1") (pintype "output"))
      (node (ref "TBD62783A-6") (pin "I2") (pinfunction "P$2_I2") (pintype "bidirectional"))
    )
    (net (code "69") (name "/TUBE6C") (class "Default")
      (node (ref "SR-6") (pin "2") (pinfunction "QC_2") (pintype "output"))
      (node (ref "TBD62783A-6") (pin "I3") (pinfunction "P$3_I3") (pintype "bidirectional"))
    )
    (net (code "70") (name "/TUBE6D") (class "Default")
      (node (ref "SR-6") (pin "3") (pinfunction "QD_3") (pintype "output"))
      (node (ref "TBD62783A-6") (pin "I4") (pinfunction "P$4_I4") (pintype "bidirectional"))
    )
    (net (code "71") (name "/TUBE6DP") (class "Default")
      (node (ref "TBD62783A-6") (pin "I8") (pinfunction "P$8_I8") (pintype "bidirectional"))
    )
    (net (code "72") (name "/TUBE6E") (class "Default")
      (node (ref "SR-6") (pin "4") (pinfunction "QE_4") (pintype "output"))
      (node (ref "TBD62783A-6") (pin "I5") (pinfunction "P$5_I5") (pintype "bidirectional"))
    )
    (net (code "73") (name "/TUBE6F") (class "Default")
      (node (ref "SR-6") (pin "5") (pinfunction "QF_5") (pintype "output"))
      (node (ref "TBD62783A-6") (pin "I6") (pinfunction "P$6_I6") (pintype "bidirectional"))
    )
    (net (code "74") (name "/TUBE6G") (class "Default")
      (node (ref "SR-6") (pin "6") (pinfunction "QG_6") (pintype "output"))
      (node (ref "TBD62783A-6") (pin "I7") (pinfunction "P$7_I7") (pintype "bidirectional"))
    )
    (net (code "75") (name "/TUBE_1_ENABLE") (class "Default")
      (node (ref "SR-1") (pin "13") (pinfunction "~{OE}_13") (pintype "input"))
      (node (ref "U2") (pin "32") (pinfunction "P3.0/PM_UCA2STE_32") (pintype "bidirectional"))
    )
    (net (code "76") (name "/TUBE_2_ENABLE") (class "Default")
      (node (ref "SR-2") (pin "13") (pinfunction "~{OE}_13") (pintype "input"))
      (node (ref "U2") (pin "33") (pinfunction "P3.1/PM_UCA2CLK_33") (pintype "bidirectional"))
    )
    (net (code "77") (name "/TUBE_3_ENABLE") (class "Default")
      (node (ref "SR-3") (pin "13") (pinfunction "~{OE}_13") (pintype "input"))
      (node (ref "U2") (pin "34") (pinfunction "P3.2/PM_UCA2RXD/PM_UCA2SOMI_34") (pintype "bidirectional"))
    )
    (net (code "78") (name "/TUBE_4_ENABLE") (class "Default")
      (node (ref "SR-4") (pin "13") (pinfunction "~{OE}_13") (pintype "input"))
      (node (ref "U2") (pin "35") (pinfunction "P3.3/PM_UCA2TXD/PM_UCA2SIMO_35") (pintype "bidirectional"))
    )
    (net (code "79") (name "/TUBE_5_ENABLE") (class "Default")
      (node (ref "SR-5") (pin "13") (pinfunction "~{OE}_13") (pintype "input"))
      (node (ref "U2") (pin "36") (pinfunction "P3.4/PM_UCB2STE_36") (pintype "bidirectional"))
    )
    (net (code "80") (name "/TUBE_6_ENABLE") (class "Default")
      (node (ref "SR-6") (pin "13") (pinfunction "~{OE}_13") (pintype "input"))
      (node (ref "U2") (pin "37") (pinfunction "P3.5/PM_UCB2CLK_37") (pintype "bidirectional"))
    )
    (net (code "81") (name "/TX_1.3") (class "Default")
      (node (ref "JTAG") (pin "5") (pinfunction "5_5") (pintype "passive"))
      (node (ref "U2") (pin "7") (pinfunction "P1.3/UCA0TXD/UCA0SIMO_7") (pintype "bidirectional"))
    )
    (net (code "82") (name "/VCC") (class "Default")
      (node (ref "SR-2") (pin "16") (pinfunction "VCC_16") (pintype "power_in"))
    )
    (net (code "83") (name "/~{RST}") (class "Default")
      (node (ref "C14") (pin "1") (pinfunction "1_1") (pintype "passive"))
      (node (ref "R6") (pin "1") (pinfunction "1_1") (pintype "passive"))
      (node (ref "SW1") (pin "B2") (pinfunction "2_B2") (pintype "passive"))
      (node (ref "U2") (pin "83") (pinfunction "RSTN/NMI_83") (pintype "bidirectional"))
    )
    (net (code "84") (name "GND") (class "Default")
      (node (ref "+5VIN") (pin "GND") (pinfunction "GND_GND") (pintype "bidirectional"))
      (node (ref "+5VIN") (pin "GNDBREAK") (pinfunction "GNDBREAK_GNDBREAK") (pintype "bidirectional"))
      (node (ref "C1") (pin "2") (pinfunction "2_2") (pintype "passive"))
      (node (ref "C10") (pin "1") (pinfunction "1_1") (pintype "passive"))
      (node (ref "C11") (pin "1") (pinfunction "1_1") (pintype "passive"))
      (node (ref "C12") (pin "-") (pinfunction "-_-") (pintype "passive"))
      (node (ref "C13") (pin "-") (pinfunction "-_-") (pintype "passive"))
      (node (ref "C14") (pin "2") (pinfunction "2_2") (pintype "passive"))
      (node (ref "C15") (pin "-") (pinfunction "-_-") (pintype "passive"))
      (node (ref "C2") (pin "2") (pinfunction "2_2") (pintype "passive"))
      (node (ref "C3") (pin "2") (pinfunction "2_2") (pintype "passive"))
      (node (ref "C4") (pin "2") (pinfunction "2_2") (pintype "passive"))
      (node (ref "C5") (pin "-") (pinfunction "-_-") (pintype "passive"))
      (node (ref "C6") (pin "2") (pinfunction "2_2") (pintype "passive"))
      (node (ref "C7") (pin "2") (pinfunction "2_2") (pintype "passive"))
      (node (ref "C8") (pin "1") (pinfunction "1_1") (pintype "passive"))
      (node (ref "C9") (pin "1") (pinfunction "1_1") (pintype "passive"))
      (node (ref "D1") (pin "C") (pinfunction "C_C") (pintype "passive"))
      (node (ref "JTAG") (pin "1") (pinfunction "1_1") (pintype "passive"))
      (node (ref "R2") (pin "1") (pinfunction "1_1") (pintype "passive"))
      (node (ref "R5") (pin "1") (pinfunction "1_1") (pintype "passive"))
      (node (ref "R8") (pin "1") (pinfunction "1_1") (pintype "passive"))
      (node (ref "SR-1") (pin "8") (pinfunction "GND_8") (pintype "power_in"))
      (node (ref "SR-2") (pin "8") (pinfunction "GND_8") (pintype "power_in"))
      (node (ref "SR-3") (pin "8") (pinfunction "GND_8") (pintype "power_in"))
      (node (ref "SR-4") (pin "8") (pinfunction "GND_8") (pintype "power_in"))
      (node (ref "SR-5") (pin "8") (pinfunction "GND_8") (pintype "power_in"))
      (node (ref "SR-6") (pin "8") (pinfunction "GND_8") (pintype "power_in"))
      (node (ref "SW1") (pin "A2") (pinfunction "1_A2") (pintype "passive"))
      (node (ref "TBD62783A-1") (pin "GND") (pinfunction "P$10_GND") (pintype "bidirectional"))
      (node (ref "TBD62783A-2") (pin "GND") (pinfunction "P$10_GND") (pintype "bidirectional"))
      (node (ref "TBD62783A-3") (pin "GND") (pinfunction "P$10_GND") (pintype "bidirectional"))
      (node (ref "TBD62783A-4") (pin "GND") (pinfunction "P$10_GND") (pintype "bidirectional"))
      (node (ref "TBD62783A-5") (pin "GND") (pinfunction "P$10_GND") (pintype "bidirectional"))
      (node (ref "TBD62783A-6") (pin "GND") (pinfunction "P$10_GND") (pintype "bidirectional"))
      (node (ref "U$1") (pin "P$3") (pinfunction "OUT-_P$3") (pintype "bidirectional"))
      (node (ref "U$1") (pin "P$4") (pinfunction "IN-_P$4") (pintype "bidirectional"))
      (node (ref "U2") (pin "15") (pinfunction "DVSS1_15") (pintype "power_in"))
      (node (ref "U2") (pin "40") (pinfunction "AVSS3_40") (pintype "power_in"))
      (node (ref "U2") (pin "43") (pinfunction "AVSS1_43") (pintype "power_in"))
      (node (ref "U2") (pin "72") (pinfunction "DVSS2_72") (pintype "power_in"))
      (node (ref "U2") (pin "82") (pinfunction "DVSS3_82") (pintype "power_in"))
      (node (ref "U2") (pin "84") (pinfunction "AVSS2_84") (pintype "power_in"))
      (node (ref "VFD1-H1") (pin "1") (pinfunction "GND_1") (pintype "bidirectional"))
      (node (ref "VFD2-H2") (pin "1") (pinfunction "GND_1") (pintype "bidirectional"))
      (node (ref "VFD3-M1") (pin "1") (pinfunction "GND_1") (pintype "bidirectional"))
      (node (ref "VFD4-M2") (pin "1") (pinfunction "GND_1") (pintype "bidirectional"))
      (node (ref "VFD5-S1") (pin "1") (pinfunction "GND_1") (pintype "bidirectional"))
      (node (ref "VFD6-S2") (pin "1") (pinfunction "GND_1") (pintype "bidirectional"))
    )
    (net (code "85") (name "Net-(+1.65VREG-ADJ)") (class "Default")
      (node (ref "+1.65VREG") (pin "1") (pinfunction "ADJ_1") (pintype "input"))
      (node (ref "R7") (pin "1") (pinfunction "1_1") (pintype "passive"))
      (node (ref "R8") (pin "2") (pinfunction "2_2") (pintype "passive"))
    )
    (net (code "86") (name "Net-(+3.3VREG-ADJ{slash}GND)") (class "Default")
      (node (ref "+3.3VREG") (pin "3") (pinfunction "ADJ/GND_3") (pintype "output"))
      (node (ref "R4") (pin "1") (pinfunction "1_1") (pintype "passive"))
      (node (ref "R5") (pin "2") (pinfunction "2_2") (pintype "passive"))
    )
    (net (code "87") (name "Net-(D1-PadA)") (class "Default")
      (node (ref "D1") (pin "A") (pinfunction "A_A") (pintype "passive"))
      (node (ref "R3") (pin "1") (pinfunction "1_1") (pintype "passive"))
    )
    (net (code "88") (name "Net-(TBD62783A-1-P$11)") (class "Default")
      (node (ref "TBD62783A-1") (pin "O8") (pinfunction "P$11_O8") (pintype "bidirectional"))
      (node (ref "VFD1-H1") (pin "10") (pinfunction "H_10") (pintype "bidirectional"))
    )
    (net (code "89") (name "Net-(TBD62783A-1-P$12)") (class "Default")
      (node (ref "TBD62783A-1") (pin "O7") (pinfunction "P$12_O7") (pintype "bidirectional"))
      (node (ref "VFD1-H1") (pin "9") (pinfunction "G_9") (pintype "bidirectional"))
    )
    (net (code "90") (name "Net-(TBD62783A-1-P$13)") (class "Default")
      (node (ref "TBD62783A-1") (pin "O6") (pinfunction "P$13_O6") (pintype "bidirectional"))
      (node (ref "VFD1-H1") (pin "8") (pinfunction "F_8") (pintype "bidirectional"))
    )
    (net (code "91") (name "Net-(TBD62783A-1-P$14)") (class "Default")
      (node (ref "TBD62783A-1") (pin "O5") (pinfunction "P$14_O5") (pintype "bidirectional"))
      (node (ref "VFD1-H1") (pin "7") (pinfunction "E_7") (pintype "bidirectional"))
    )
    (net (code "92") (name "Net-(TBD62783A-1-P$15)") (class "Default")
      (node (ref "TBD62783A-1") (pin "O4") (pinfunction "P$15_O4") (pintype "bidirectional"))
      (node (ref "VFD1-H1") (pin "6") (pinfunction "D_6") (pintype "bidirectional"))
    )
    (net (code "93") (name "Net-(TBD62783A-1-P$16)") (class "Default")
      (node (ref "TBD62783A-1") (pin "O3") (pinfunction "P$16_O3") (pintype "bidirectional"))
      (node (ref "VFD1-H1") (pin "5") (pinfunction "C_5") (pintype "bidirectional"))
    )
    (net (code "94") (name "Net-(TBD62783A-1-P$17)") (class "Default")
      (node (ref "TBD62783A-1") (pin "O2") (pinfunction "P$17_O2") (pintype "bidirectional"))
      (node (ref "VFD1-H1") (pin "4") (pinfunction "B_4") (pintype "bidirectional"))
    )
    (net (code "95") (name "Net-(TBD62783A-1-P$18)") (class "Default")
      (node (ref "TBD62783A-1") (pin "O1") (pinfunction "P$18_O1") (pintype "bidirectional"))
      (node (ref "VFD1-H1") (pin "3") (pinfunction "A_3") (pintype "bidirectional"))
    )
    (net (code "96") (name "Net-(TBD62783A-2-P$11)") (class "Default")
      (node (ref "TBD62783A-2") (pin "O8") (pinfunction "P$11_O8") (pintype "bidirectional"))
      (node (ref "VFD2-H2") (pin "10") (pinfunction "H_10") (pintype "bidirectional"))
    )
    (net (code "97") (name "Net-(TBD62783A-2-P$12)") (class "Default")
      (node (ref "TBD62783A-2") (pin "O7") (pinfunction "P$12_O7") (pintype "bidirectional"))
      (node (ref "VFD2-H2") (pin "9") (pinfunction "G_9") (pintype "bidirectional"))
    )
    (net (code "98") (name "Net-(TBD62783A-2-P$13)") (class "Default")
      (node (ref "TBD62783A-2") (pin "O6") (pinfunction "P$13_O6") (pintype "bidirectional"))
      (node (ref "VFD2-H2") (pin "8") (pinfunction "F_8") (pintype "bidirectional"))
    )
    (net (code "99") (name "Net-(TBD62783A-2-P$14)") (class "Default")
      (node (ref "TBD62783A-2") (pin "O5") (pinfunction "P$14_O5") (pintype "bidirectional"))
      (node (ref "VFD2-H2") (pin "7") (pinfunction "E_7") (pintype "bidirectional"))
    )
    (net (code "100") (name "Net-(TBD62783A-2-P$15)") (class "Default")
      (node (ref "TBD62783A-2") (pin "O4") (pinfunction "P$15_O4") (pintype "bidirectional"))
      (node (ref "VFD2-H2") (pin "6") (pinfunction "D_6") (pintype "bidirectional"))
    )
    (net (code "101") (name "Net-(TBD62783A-2-P$16)") (class "Default")
      (node (ref "TBD62783A-2") (pin "O3") (pinfunction "P$16_O3") (pintype "bidirectional"))
      (node (ref "VFD2-H2") (pin "5") (pinfunction "C_5") (pintype "bidirectional"))
    )
    (net (code "102") (name "Net-(TBD62783A-2-P$17)") (class "Default")
      (node (ref "TBD62783A-2") (pin "O2") (pinfunction "P$17_O2") (pintype "bidirectional"))
      (node (ref "VFD2-H2") (pin "4") (pinfunction "B_4") (pintype "bidirectional"))
    )
    (net (code "103") (name "Net-(TBD62783A-2-P$18)") (class "Default")
      (node (ref "TBD62783A-2") (pin "O1") (pinfunction "P$18_O1") (pintype "bidirectional"))
      (node (ref "VFD2-H2") (pin "3") (pinfunction "A_3") (pintype "bidirectional"))
    )
    (net (code "104") (name "Net-(TBD62783A-3-P$11)") (class "Default")
      (node (ref "TBD62783A-3") (pin "O8") (pinfunction "P$11_O8") (pintype "bidirectional"))
      (node (ref "VFD3-M1") (pin "10") (pinfunction "H_10") (pintype "bidirectional"))
    )
    (net (code "105") (name "Net-(TBD62783A-3-P$12)") (class "Default")
      (node (ref "TBD62783A-3") (pin "O7") (pinfunction "P$12_O7") (pintype "bidirectional"))
      (node (ref "VFD3-M1") (pin "9") (pinfunction "G_9") (pintype "bidirectional"))
    )
    (net (code "106") (name "Net-(TBD62783A-3-P$13)") (class "Default")
      (node (ref "TBD62783A-3") (pin "O6") (pinfunction "P$13_O6") (pintype "bidirectional"))
      (node (ref "VFD3-M1") (pin "8") (pinfunction "F_8") (pintype "bidirectional"))
    )
    (net (code "107") (name "Net-(TBD62783A-3-P$14)") (class "Default")
      (node (ref "TBD62783A-3") (pin "O5") (pinfunction "P$14_O5") (pintype "bidirectional"))
      (node (ref "VFD3-M1") (pin "7") (pinfunction "E_7") (pintype "bidirectional"))
    )
    (net (code "108") (name "Net-(TBD62783A-3-P$15)") (class "Default")
      (node (ref "TBD62783A-3") (pin "O4") (pinfunction "P$15_O4") (pintype "bidirectional"))
      (node (ref "VFD3-M1") (pin "6") (pinfunction "D_6") (pintype "bidirectional"))
    )
    (net (code "109") (name "Net-(TBD62783A-3-P$16)") (class "Default")
      (node (ref "TBD62783A-3") (pin "O3") (pinfunction "P$16_O3") (pintype "bidirectional"))
      (node (ref "VFD3-M1") (pin "5") (pinfunction "C_5") (pintype "bidirectional"))
    )
    (net (code "110") (name "Net-(TBD62783A-3-P$17)") (class "Default")
      (node (ref "TBD62783A-3") (pin "O2") (pinfunction "P$17_O2") (pintype "bidirectional"))
      (node (ref "VFD3-M1") (pin "4") (pinfunction "B_4") (pintype "bidirectional"))
    )
    (net (code "111") (name "Net-(TBD62783A-3-P$18)") (class "Default")
      (node (ref "TBD62783A-3") (pin "O1") (pinfunction "P$18_O1") (pintype "bidirectional"))
      (node (ref "VFD3-M1") (pin "3") (pinfunction "A_3") (pintype "bidirectional"))
    )
    (net (code "112") (name "Net-(TBD62783A-4-P$11)") (class "Default")
      (node (ref "TBD62783A-4") (pin "O8") (pinfunction "P$11_O8") (pintype "bidirectional"))
      (node (ref "VFD4-M2") (pin "10") (pinfunction "H_10") (pintype "bidirectional"))
    )
    (net (code "113") (name "Net-(TBD62783A-4-P$12)") (class "Default")
      (node (ref "TBD62783A-4") (pin "O7") (pinfunction "P$12_O7") (pintype "bidirectional"))
      (node (ref "VFD4-M2") (pin "9") (pinfunction "G_9") (pintype "bidirectional"))
    )
    (net (code "114") (name "Net-(TBD62783A-4-P$13)") (class "Default")
      (node (ref "TBD62783A-4") (pin "O6") (pinfunction "P$13_O6") (pintype "bidirectional"))
      (node (ref "VFD4-M2") (pin "8") (pinfunction "F_8") (pintype "bidirectional"))
    )
    (net (code "115") (name "Net-(TBD62783A-4-P$14)") (class "Default")
      (node (ref "TBD62783A-4") (pin "O5") (pinfunction "P$14_O5") (pintype "bidirectional"))
      (node (ref "VFD4-M2") (pin "7") (pinfunction "E_7") (pintype "bidirectional"))
    )
    (net (code "116") (name "Net-(TBD62783A-4-P$15)") (class "Default")
      (node (ref "TBD62783A-4") (pin "O4") (pinfunction "P$15_O4") (pintype "bidirectional"))
      (node (ref "VFD4-M2") (pin "6") (pinfunction "D_6") (pintype "bidirectional"))
    )
    (net (code "117") (name "Net-(TBD62783A-4-P$16)") (class "Default")
      (node (ref "TBD62783A-4") (pin "O3") (pinfunction "P$16_O3") (pintype "bidirectional"))
      (node (ref "VFD4-M2") (pin "5") (pinfunction "C_5") (pintype "bidirectional"))
    )
    (net (code "118") (name "Net-(TBD62783A-4-P$17)") (class "Default")
      (node (ref "TBD62783A-4") (pin "O2") (pinfunction "P$17_O2") (pintype "bidirectional"))
      (node (ref "VFD4-M2") (pin "4") (pinfunction "B_4") (pintype "bidirectional"))
    )
    (net (code "119") (name "Net-(TBD62783A-4-P$18)") (class "Default")
      (node (ref "TBD62783A-4") (pin "O1") (pinfunction "P$18_O1") (pintype "bidirectional"))
      (node (ref "VFD4-M2") (pin "3") (pinfunction "A_3") (pintype "bidirectional"))
    )
    (net (code "120") (name "Net-(TBD62783A-5-P$11)") (class "Default")
      (node (ref "TBD62783A-5") (pin "O8") (pinfunction "P$11_O8") (pintype "bidirectional"))
      (node (ref "VFD5-S1") (pin "10") (pinfunction "H_10") (pintype "bidirectional"))
    )
    (net (code "121") (name "Net-(TBD62783A-5-P$12)") (class "Default")
      (node (ref "TBD62783A-5") (pin "O7") (pinfunction "P$12_O7") (pintype "bidirectional"))
      (node (ref "VFD5-S1") (pin "9") (pinfunction "G_9") (pintype "bidirectional"))
    )
    (net (code "122") (name "Net-(TBD62783A-5-P$13)") (class "Default")
      (node (ref "TBD62783A-5") (pin "O6") (pinfunction "P$13_O6") (pintype "bidirectional"))
      (node (ref "VFD5-S1") (pin "8") (pinfunction "F_8") (pintype "bidirectional"))
    )
    (net (code "123") (name "Net-(TBD62783A-5-P$14)") (class "Default")
      (node (ref "TBD62783A-5") (pin "O5") (pinfunction "P$14_O5") (pintype "bidirectional"))
      (node (ref "VFD5-S1") (pin "7") (pinfunction "E_7") (pintype "bidirectional"))
    )
    (net (code "124") (name "Net-(TBD62783A-5-P$15)") (class "Default")
      (node (ref "TBD62783A-5") (pin "O4") (pinfunction "P$15_O4") (pintype "bidirectional"))
      (node (ref "VFD5-S1") (pin "6") (pinfunction "D_6") (pintype "bidirectional"))
    )
    (net (code "125") (name "Net-(TBD62783A-5-P$16)") (class "Default")
      (node (ref "TBD62783A-5") (pin "O3") (pinfunction "P$16_O3") (pintype "bidirectional"))
      (node (ref "VFD5-S1") (pin "5") (pinfunction "C_5") (pintype "bidirectional"))
    )
    (net (code "126") (name "Net-(TBD62783A-5-P$17)") (class "Default")
      (node (ref "TBD62783A-5") (pin "O2") (pinfunction "P$17_O2") (pintype "bidirectional"))
      (node (ref "VFD5-S1") (pin "4") (pinfunction "B_4") (pintype "bidirectional"))
    )
    (net (code "127") (name "Net-(TBD62783A-5-P$18)") (class "Default")
      (node (ref "TBD62783A-5") (pin "O1") (pinfunction "P$18_O1") (pintype "bidirectional"))
      (node (ref "VFD5-S1") (pin "3") (pinfunction "A_3") (pintype "bidirectional"))
    )
    (net (code "128") (name "Net-(TBD62783A-6-P$11)") (class "Default")
      (node (ref "TBD62783A-6") (pin "O8") (pinfunction "P$11_O8") (pintype "bidirectional"))
      (node (ref "VFD6-S2") (pin "10") (pinfunction "H_10") (pintype "bidirectional"))
    )
    (net (code "129") (name "Net-(TBD62783A-6-P$12)") (class "Default")
      (node (ref "TBD62783A-6") (pin "O7") (pinfunction "P$12_O7") (pintype "bidirectional"))
      (node (ref "VFD6-S2") (pin "9") (pinfunction "G_9") (pintype "bidirectional"))
    )
    (net (code "130") (name "Net-(TBD62783A-6-P$13)") (class "Default")
      (node (ref "TBD62783A-6") (pin "O6") (pinfunction "P$13_O6") (pintype "bidirectional"))
      (node (ref "VFD6-S2") (pin "8") (pinfunction "F_8") (pintype "bidirectional"))
    )
    (net (code "131") (name "Net-(TBD62783A-6-P$14)") (class "Default")
      (node (ref "TBD62783A-6") (pin "O5") (pinfunction "P$14_O5") (pintype "bidirectional"))
      (node (ref "VFD6-S2") (pin "7") (pinfunction "E_7") (pintype "bidirectional"))
    )
    (net (code "132") (name "Net-(TBD62783A-6-P$15)") (class "Default")
      (node (ref "TBD62783A-6") (pin "O4") (pinfunction "P$15_O4") (pintype "bidirectional"))
      (node (ref "VFD6-S2") (pin "6") (pinfunction "D_6") (pintype "bidirectional"))
    )
    (net (code "133") (name "Net-(TBD62783A-6-P$16)") (class "Default")
      (node (ref "TBD62783A-6") (pin "O3") (pinfunction "P$16_O3") (pintype "bidirectional"))
      (node (ref "VFD6-S2") (pin "5") (pinfunction "C_5") (pintype "bidirectional"))
    )
    (net (code "134") (name "Net-(TBD62783A-6-P$17)") (class "Default")
      (node (ref "TBD62783A-6") (pin "O2") (pinfunction "P$17_O2") (pintype "bidirectional"))
      (node (ref "VFD6-S2") (pin "4") (pinfunction "B_4") (pintype "bidirectional"))
    )
    (net (code "135") (name "Net-(TBD62783A-6-P$18)") (class "Default")
      (node (ref "TBD62783A-6") (pin "O1") (pinfunction "P$18_O1") (pintype "bidirectional"))
      (node (ref "VFD6-S2") (pin "3") (pinfunction "A_3") (pintype "bidirectional"))
    )
    (net (code "136") (name "Net-(U2-DCOR)") (class "Default")
      (node (ref "R2") (pin "2") (pinfunction "2_2") (pintype "passive"))
      (node (ref "U2") (pin "44") (pinfunction "DCOR_44") (pintype "input"))
    )
    (net (code "137") (name "Net-(U2-PJ.0{slash}LFXIN)") (class "Default")
      (node (ref "C11") (pin "2") (pinfunction "2_2") (pintype "passive"))
      (node (ref "U2") (pin "41") (pinfunction "PJ.0/LFXIN_41") (pintype "bidirectional"))
      (node (ref "Y2") (pin "P$1") (pinfunction "1_P$1") (pintype "passive"))
    )
    (net (code "138") (name "Net-(U2-PJ.1{slash}LFXOUT)") (class "Default")
      (node (ref "C10") (pin "2") (pinfunction "2_2") (pintype "passive"))
      (node (ref "U2") (pin "42") (pinfunction "PJ.1/LFXOUT_42") (pintype "bidirectional"))
      (node (ref "Y2") (pin "P$2") (pinfunction "2_P$2") (pintype "passive"))
    )
    (net (code "139") (name "Net-(U2-PJ.2{slash}HFXOUT)") (class "Default")
      (node (ref "C8") (pin "2") (pinfunction "2_2") (pintype "passive"))
      (node (ref "U2") (pin "85") (pinfunction "PJ.2/HFXOUT_85") (pintype "bidirectional"))
      (node (ref "Y1") (pin "3") (pinfunction "2_3") (pintype "passive"))
    )
    (net (code "140") (name "Net-(U2-PJ.3{slash}HFXIN)") (class "Default")
      (node (ref "C9") (pin "2") (pinfunction "2_2") (pintype "passive"))
      (node (ref "U2") (pin "86") (pinfunction "PJ.3/HFXIN_86") (pintype "bidirectional"))
      (node (ref "Y1") (pin "1") (pinfunction "1_1") (pintype "passive"))
    )
    (net (code "141") (name "Net-(U2-VCORE)") (class "Default")
      (node (ref "C6") (pin "1") (pinfunction "1_1") (pintype "passive"))
      (node (ref "C7") (pin "1") (pinfunction "1_1") (pintype "passive"))
      (node (ref "L1") (pin "2") (pinfunction "2_2") (pintype "passive"))
      (node (ref "U2") (pin "12") (pinfunction "VCORE_12") (pintype "power_in"))
    )
    (net (code "142") (name "Net-(U2-VSW)") (class "Default")
      (node (ref "L1") (pin "1") (pinfunction "1_1") (pintype "passive"))
      (node (ref "U2") (pin "14") (pinfunction "VSW_14") (pintype "power_in"))
    )
    (net (code "143") (name "unconnected-(SR-1-QH-Pad7)") (class "Default")
      (node (ref "SR-1") (pin "7") (pinfunction "QH_7") (pintype "output"))
    )
    (net (code "144") (name "unconnected-(SR-1-QH_2-Pad9)") (class "Default")
      (node (ref "SR-1") (pin "9") (pinfunction "QH_2_9") (pintype "output"))
    )
    (net (code "145") (name "unconnected-(SR-2-QH-Pad7)") (class "Default")
      (node (ref "SR-2") (pin "7") (pinfunction "QH_7") (pintype "output"))
    )
    (net (code "146") (name "unconnected-(SR-2-QH_2-Pad9)") (class "Default")
      (node (ref "SR-2") (pin "9") (pinfunction "QH_2_9") (pintype "output"))
    )
    (net (code "147") (name "unconnected-(SR-3-QH-Pad7)") (class "Default")
      (node (ref "SR-3") (pin "7") (pinfunction "QH_7") (pintype "output"))
    )
    (net (code "148") (name "unconnected-(SR-3-QH_2-Pad9)") (class "Default")
      (node (ref "SR-3") (pin "9") (pinfunction "QH_2_9") (pintype "output"))
    )
    (net (code "149") (name "unconnected-(SR-4-QH-Pad7)") (class "Default")
      (node (ref "SR-4") (pin "7") (pinfunction "QH_7") (pintype "output"))
    )
    (net (code "150") (name "unconnected-(SR-4-QH_2-Pad9)") (class "Default")
      (node (ref "SR-4") (pin "9") (pinfunction "QH_2_9") (pintype "output"))
    )
    (net (code "151") (name "unconnected-(SR-5-QH-Pad7)") (class "Default")
      (node (ref "SR-5") (pin "7") (pinfunction "QH_7") (pintype "output"))
    )
    (net (code "152") (name "unconnected-(SR-5-QH_2-Pad9)") (class "Default")
      (node (ref "SR-5") (pin "9") (pinfunction "QH_2_9") (pintype "output"))
    )
    (net (code "153") (name "unconnected-(SR-6-QH-Pad7)") (class "Default")
      (node (ref "SR-6") (pin "7") (pinfunction "QH_7") (pintype "output"))
    )
    (net (code "154") (name "unconnected-(SR-6-QH_2-Pad9)") (class "Default")
      (node (ref "SR-6") (pin "9") (pinfunction "QH_2_9") (pintype "output"))
    )
    (net (code "155") (name "unconnected-(U2-P1.0{slash}UCA0STE-Pad4)") (class "Default")
      (node (ref "U2") (pin "4") (pinfunction "P1.0/UCA0STE_4") (pintype "bidirectional"))
    )
    (net (code "156") (name "unconnected-(U2-P1.1{slash}UCA0CLK-Pad5)") (class "Default")
      (node (ref "U2") (pin "5") (pinfunction "P1.1/UCA0CLK_5") (pintype "bidirectional"))
    )
    (net (code "157") (name "unconnected-(U2-P1.4{slash}UCB0STE-Pad8)") (class "Default")
      (node (ref "U2") (pin "8") (pinfunction "P1.4/UCB0STE_8") (pintype "bidirectional"))
    )
    (net (code "158") (name "unconnected-(U2-P1.5{slash}UCB0CLK-Pad9)") (class "Default")
      (node (ref "U2") (pin "9") (pinfunction "P1.5/UCB0CLK_9") (pintype "bidirectional"))
    )
    (net (code "159") (name "unconnected-(U2-P1.6{slash}UCB0SIMO{slash}UCB0SDA-Pad10)") (class "Default")
      (node (ref "U2") (pin "10") (pinfunction "P1.6/UCB0SIMO/UCB0SDA_10") (pintype "bidirectional"))
    )
    (net (code "160") (name "unconnected-(U2-P1.7{slash}UCB0SOMI{slash}UCB0SCL-Pad11)") (class "Default")
      (node (ref "U2") (pin "11") (pinfunction "P1.7/UCB0SOMI/UCB0SCL_11") (pintype "bidirectional"))
    )
    (net (code "161") (name "unconnected-(U2-P2.0{slash}PM_UCA1STE-Pad16)") (class "Default")
      (node (ref "U2") (pin "16") (pinfunction "P2.0/PM_UCA1STE_16") (pintype "bidirectional"))
    )
    (net (code "162") (name "unconnected-(U2-P2.1{slash}PM_UCA1CLK-Pad17)") (class "Default")
      (node (ref "U2") (pin "17") (pinfunction "P2.1/PM_UCA1CLK_17") (pintype "bidirectional"))
    )
    (net (code "163") (name "unconnected-(U2-P2.2{slash}PM_UCA1RXD{slash}PM_UCA1SOMI-Pad18)") (class "Default")
      (node (ref "U2") (pin "18") (pinfunction "P2.2/PM_UCA1RXD/PM_UCA1SOMI_18") (pintype "bidirectional"))
    )
    (net (code "164") (name "unconnected-(U2-P2.3{slash}PM_UCA1TXD{slash}PM_UCA1SIMO-Pad19)") (class "Default")
      (node (ref "U2") (pin "19") (pinfunction "P2.3/PM_UCA1TXD/PM_UCA1SIMO_19") (pintype "bidirectional"))
    )
    (net (code "165") (name "unconnected-(U2-P2.7{slash}PM_TA0.4-Pad23)") (class "Default")
      (node (ref "U2") (pin "23") (pinfunction "P2.7/PM_TA0.4_23") (pintype "bidirectional"))
    )
    (net (code "166") (name "unconnected-(U2-P3.6{slash}PM_UCB2SIMO{slash}PM_UCB2SDA-Pad38)") (class "Default")
      (node (ref "U2") (pin "38") (pinfunction "P3.6/PM_UCB2SIMO/PM_UCB2SDA_38") (pintype "bidirectional"))
    )
    (net (code "167") (name "unconnected-(U2-P3.7{slash}PM_UCB2SOMI{slash}PM_UCB2SCL-Pad39)") (class "Default")
      (node (ref "U2") (pin "39") (pinfunction "P3.7/PM_UCB2SOMI/PM_UCB2SCL_39") (pintype "bidirectional"))
    )
    (net (code "168") (name "unconnected-(U2-P5.0{slash}A5-Pad64)") (class "Default")
      (node (ref "U2") (pin "64") (pinfunction "P5.0/A5_64") (pintype "bidirectional"))
    )
    (net (code "169") (name "unconnected-(U2-P5.1{slash}A4-Pad65)") (class "Default")
      (node (ref "U2") (pin "65") (pinfunction "P5.1/A4_65") (pintype "bidirectional"))
    )
    (net (code "170") (name "unconnected-(U2-P5.2{slash}A3-Pad66)") (class "Default")
      (node (ref "U2") (pin "66") (pinfunction "P5.2/A3_66") (pintype "bidirectional"))
    )
    (net (code "171") (name "unconnected-(U2-P5.3{slash}A2-Pad67)") (class "Default")
      (node (ref "U2") (pin "67") (pinfunction "P5.3/A2_67") (pintype "bidirectional"))
    )
    (net (code "172") (name "unconnected-(U2-P5.4{slash}A1-Pad68)") (class "Default")
      (node (ref "U2") (pin "68") (pinfunction "P5.4/A1_68") (pintype "bidirectional"))
    )
    (net (code "173") (name "unconnected-(U2-P5.5{slash}A0-Pad69)") (class "Default")
      (node (ref "U2") (pin "69") (pinfunction "P5.5/A0_69") (pintype "bidirectional"))
    )
    (net (code "174") (name "unconnected-(U2-P5.6{slash}TA2.1{slash}VREF+{slash}VEREF+{slash}C1.7-Pad70)") (class "Default")
      (node (ref "U2") (pin "70") (pinfunction "P5.6/TA2.1/VREF+/VEREF+/C1.7_70") (pintype "bidirectional"))
    )
    (net (code "175") (name "unconnected-(U2-P5.7{slash}TA2.2{slash}VREF-{slash}VEREF-{slash}C1.6-Pad71)") (class "Default")
      (node (ref "U2") (pin "71") (pinfunction "P5.7/TA2.2/VREF-/VEREF-/C1.6_71") (pintype "bidirectional"))
    )
    (net (code "176") (name "unconnected-(U2-P6.0{slash}A15-Pad54)") (class "Default")
      (node (ref "U2") (pin "54") (pinfunction "P6.0/A15_54") (pintype "bidirectional"))
    )
    (net (code "177") (name "unconnected-(U2-P6.2{slash}UCB1STE{slash}C1.5-Pad76)") (class "Default")
      (node (ref "U2") (pin "76") (pinfunction "P6.2/UCB1STE/C1.5_76") (pintype "bidirectional"))
    )
    (net (code "178") (name "unconnected-(U2-P6.3{slash}UCB1CLK{slash}C1.4-Pad77)") (class "Default")
      (node (ref "U2") (pin "77") (pinfunction "P6.3/UCB1CLK/C1.4_77") (pintype "bidirectional"))
    )
    (net (code "179") (name "unconnected-(U2-P6.4{slash}UCB1SIMO{slash}UCB1SDA{slash}C1.3-Pad78)") (class "Default")
      (node (ref "U2") (pin "78") (pinfunction "P6.4/UCB1SIMO/UCB1SDA/C1.3_78") (pintype "bidirectional"))
    )
    (net (code "180") (name "unconnected-(U2-P6.5{slash}UCB1SOMI{slash}UCB1SCL{slash}C1.2-Pad79)") (class "Default")
      (node (ref "U2") (pin "79") (pinfunction "P6.5/UCB1SOMI/UCB1SCL/C1.2_79") (pintype "bidirectional"))
    )
    (net (code "181") (name "unconnected-(U2-P6.6{slash}TA2.3{slash}UCB3SIMO{slash}UCB3SDA{slash}C1.1-Pad80)") (class "Default")
      (node (ref "U2") (pin "80") (pinfunction "P6.6/TA2.3/UCB3SIMO/UCB3SDA/C1.1_80") (pintype "bidirectional"))
    )
    (net (code "182") (name "unconnected-(U2-P6.7{slash}TA2.4{slash}UCB3SOMI{slash}UCB3SCL{slash}C1.0-Pad81)") (class "Default")
      (node (ref "U2") (pin "81") (pinfunction "P6.7/TA2.4/UCB3SOMI/UCB3SCL/C1.0_81") (pintype "bidirectional"))
    )
    (net (code "183") (name "unconnected-(U2-P7.0{slash}PM_SMCLK{slash}PM_DMAE0-Pad88)") (class "Default")
      (node (ref "U2") (pin "88") (pinfunction "P7.0/PM_SMCLK/PM_DMAE0_88") (pintype "bidirectional"))
    )
    (net (code "184") (name "unconnected-(U2-P7.1{slash}PM_C0OUT{slash}PM_TA0CLK-Pad89)") (class "Default")
      (node (ref "U2") (pin "89") (pinfunction "P7.1/PM_C0OUT/PM_TA0CLK_89") (pintype "bidirectional"))
    )
    (net (code "185") (name "unconnected-(U2-P7.2{slash}PM_C1OUT{slash}PM_TA1CLK-Pad90)") (class "Default")
      (node (ref "U2") (pin "90") (pinfunction "P7.2/PM_C1OUT/PM_TA1CLK_90") (pintype "bidirectional"))
    )
    (net (code "186") (name "unconnected-(U2-P7.3{slash}PM_TA0.0-Pad91)") (class "Default")
      (node (ref "U2") (pin "91") (pinfunction "P7.3/PM_TA0.0_91") (pintype "bidirectional"))
    )
    (net (code "187") (name "unconnected-(U2-P7.4{slash}PM_TA1.4{slash}C0.5-Pad26)") (class "Default")
      (node (ref "U2") (pin "26") (pinfunction "P7.4/PM_TA1.4/C0.5_26") (pintype "bidirectional"))
    )
    (net (code "188") (name "unconnected-(U2-P7.5{slash}PM_TA1.3{slash}C0.4-Pad27)") (class "Default")
      (node (ref "U2") (pin "27") (pinfunction "P7.5/PM_TA1.3/C0.4_27") (pintype "bidirectional"))
    )
    (net (code "189") (name "unconnected-(U2-P7.6{slash}PM_TA1.2{slash}C0.3-Pad28)") (class "Default")
      (node (ref "U2") (pin "28") (pinfunction "P7.6/PM_TA1.2/C0.3_28") (pintype "bidirectional"))
    )
    (net (code "190") (name "unconnected-(U2-P7.7{slash}PM_TA1.1{slash}C0.2-Pad29)") (class "Default")
      (node (ref "U2") (pin "29") (pinfunction "P7.7/PM_TA1.1/C0.2_29") (pintype "bidirectional"))
    )
    (net (code "191") (name "unconnected-(U2-P8.0{slash}UCB3STE{slash}TA1.0{slash}C0.1-Pad30)") (class "Default")
      (node (ref "U2") (pin "30") (pinfunction "P8.0/UCB3STE/TA1.0/C0.1_30") (pintype "bidirectional"))
    )
    (net (code "192") (name "unconnected-(U2-P8.1{slash}UCB3CLK{slash}TA2.0{slash}C0.0-Pad31)") (class "Default")
      (node (ref "U2") (pin "31") (pinfunction "P8.1/UCB3CLK/TA2.0/C0.0_31") (pintype "bidirectional"))
    )
    (net (code "193") (name "unconnected-(U2-P8.2{slash}TA3.2{slash}A23-Pad46)") (class "Default")
      (node (ref "U2") (pin "46") (pinfunction "P8.2/TA3.2/A23_46") (pintype "bidirectional"))
    )
    (net (code "194") (name "unconnected-(U2-P8.3{slash}TA3CLK{slash}A22-Pad47)") (class "Default")
      (node (ref "U2") (pin "47") (pinfunction "P8.3/TA3CLK/A22_47") (pintype "bidirectional"))
    )
    (net (code "195") (name "unconnected-(U2-P8.4{slash}A21-Pad48)") (class "Default")
      (node (ref "U2") (pin "48") (pinfunction "P8.4/A21_48") (pintype "bidirectional"))
    )
    (net (code "196") (name "unconnected-(U2-P8.5{slash}A20-Pad49)") (class "Default")
      (node (ref "U2") (pin "49") (pinfunction "P8.5/A20_49") (pintype "bidirectional"))
    )
    (net (code "197") (name "unconnected-(U2-P8.6{slash}A19-Pad50)") (class "Default")
      (node (ref "U2") (pin "50") (pinfunction "P8.6/A19_50") (pintype "bidirectional"))
    )
    (net (code "198") (name "unconnected-(U2-P8.7{slash}A18-Pad51)") (class "Default")
      (node (ref "U2") (pin "51") (pinfunction "P8.7/A18_51") (pintype "bidirectional"))
    )
    (net (code "199") (name "unconnected-(U2-P9.0{slash}A17-Pad52)") (class "Default")
      (node (ref "U2") (pin "52") (pinfunction "P9.0/A17_52") (pintype "bidirectional"))
    )
    (net (code "200") (name "unconnected-(U2-P9.1{slash}A16-Pad53)") (class "Default")
      (node (ref "U2") (pin "53") (pinfunction "P9.1/A16_53") (pintype "bidirectional"))
    )
    (net (code "201") (name "unconnected-(U2-P9.2{slash}TA3.3-Pad74)") (class "Default")
      (node (ref "U2") (pin "74") (pinfunction "P9.2/TA3.3_74") (pintype "bidirectional"))
    )
    (net (code "202") (name "unconnected-(U2-P9.3{slash}TA3.4-Pad75)") (class "Default")
      (node (ref "U2") (pin "75") (pinfunction "P9.3/TA3.4_75") (pintype "bidirectional"))
    )
    (net (code "203") (name "unconnected-(U2-P9.4{slash}UCA3STE-Pad96)") (class "Default")
      (node (ref "U2") (pin "96") (pinfunction "P9.4/UCA3STE_96") (pintype "bidirectional"))
    )
    (net (code "204") (name "unconnected-(U2-P9.5{slash}UCA3CLK-Pad97)") (class "Default")
      (node (ref "U2") (pin "97") (pinfunction "P9.5/UCA3CLK_97") (pintype "bidirectional"))
    )
    (net (code "205") (name "unconnected-(U2-P9.6{slash}UCA3RXD{slash}UCA3SOMI-Pad98)") (class "Default")
      (node (ref "U2") (pin "98") (pinfunction "P9.6/UCA3RXD/UCA3SOMI_98") (pintype "bidirectional"))
    )
    (net (code "206") (name "unconnected-(U2-P9.7{slash}UCA3TXD{slash}UCA3SIMO-Pad99)") (class "Default")
      (node (ref "U2") (pin "99") (pinfunction "P9.7/UCA3TXD/UCA3SIMO_99") (pintype "bidirectional"))
    )
    (net (code "207") (name "unconnected-(U2-P10.0{slash}UCB3STE-Pad100)") (class "Default")
      (node (ref "U2") (pin "100") (pinfunction "P10.0/UCB3STE_100") (pintype "bidirectional"))
    )
    (net (code "208") (name "unconnected-(U2-P10.4{slash}TA3.0{slash}C0.7-Pad24)") (class "Default")
      (node (ref "U2") (pin "24") (pinfunction "P10.4/TA3.0/C0.7_24") (pintype "bidirectional"))
    )
    (net (code "209") (name "unconnected-(U2-P10.5{slash}TA3.1{slash}C0.6-Pad25)") (class "Default")
      (node (ref "U2") (pin "25") (pinfunction "P10.5/TA3.1/C0.6_25") (pintype "bidirectional"))
    )
  )
)
